# Timer-Ruler_v3.net
KiCad netlist of a schematic drawn in EAGLE
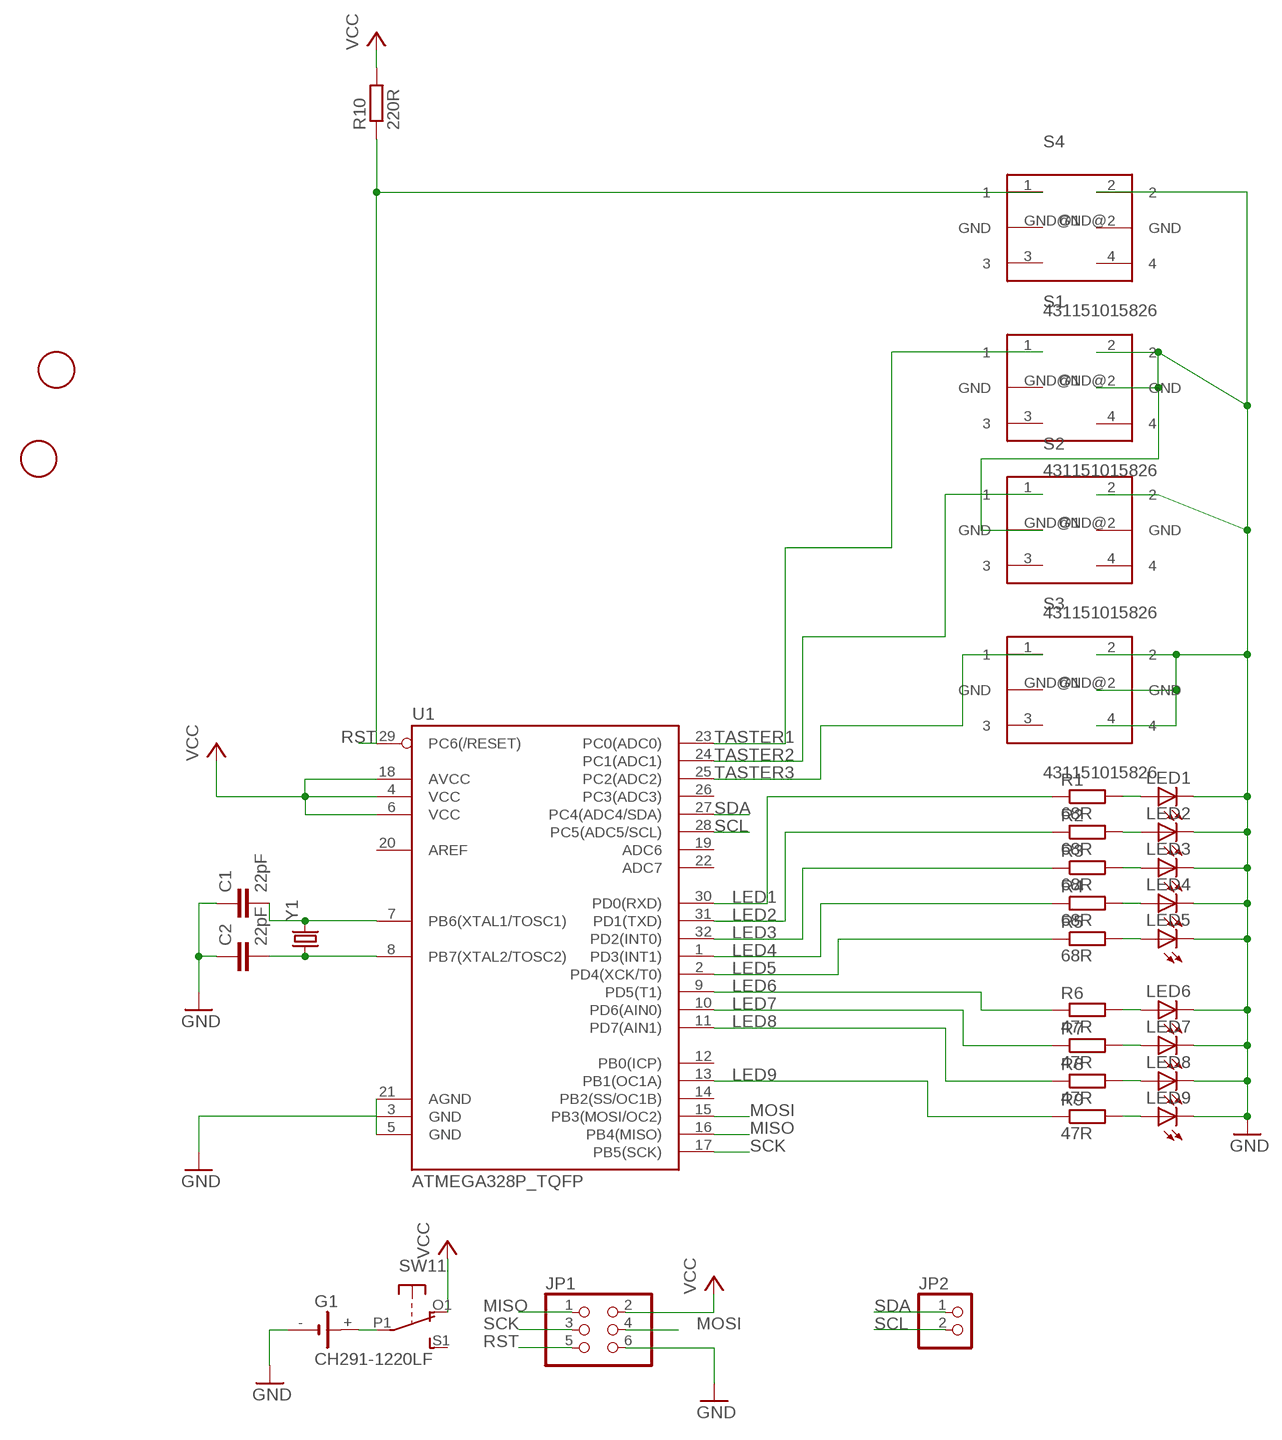
[diagram p0: schematic, sheet 1]

(export (version "E")
  (design (tool "Eeschema 10.0.6"))
  (components
    (comp (ref "C1")
      (value "22pF")
      (footprint "eagle-import:C0603")
      (libsource (lib "eagle-import") (part "C-EUC0603"))
    )
    (comp (ref "C2")
      (value "22pF")
      (footprint "eagle-import:C0603")
      (libsource (lib "eagle-import") (part "C-EUC0603"))
    )
    (comp (ref "G1")
      (value "CH291-1220LF")
      (footprint "eagle-import:CH291-1220LF")
      (libsource (lib "eagle-import") (part "CH291-1220LF"))
    )
    (comp (ref "JP1")
      (value "PINHD-2X3")
      (footprint "eagle-import:2X03")
      (libsource (lib "eagle-import") (part "PINHD-2X3"))
    )
    (comp (ref "JP2")
      (value "PINHD-1X2")
      (footprint "eagle-import:1X02")
      (libsource (lib "eagle-import") (part "PINHD-1X2"))
    )
    (comp (ref "LED1")
      (value "LEDCHIP-LED0805")
      (footprint "eagle-import:CHIP-LED0805")
      (libsource (lib "eagle-import") (part "LEDCHIP-LED0805"))
    )
    (comp (ref "LED2")
      (value "LEDCHIP-LED0805")
      (footprint "eagle-import:CHIP-LED0805")
      (libsource (lib "eagle-import") (part "LEDCHIP-LED0805"))
    )
    (comp (ref "LED3")
      (value "LEDCHIP-LED0805")
      (footprint "eagle-import:CHIP-LED0805")
      (libsource (lib "eagle-import") (part "LEDCHIP-LED0805"))
    )
    (comp (ref "LED4")
      (value "LEDCHIP-LED0805")
      (footprint "eagle-import:CHIP-LED0805")
      (libsource (lib "eagle-import") (part "LEDCHIP-LED0805"))
    )
    (comp (ref "LED5")
      (value "LEDCHIP-LED0805")
      (footprint "eagle-import:CHIP-LED0805")
      (libsource (lib "eagle-import") (part "LEDCHIP-LED0805"))
    )
    (comp (ref "LED6")
      (value "LEDCHIP-LED0805")
      (footprint "eagle-import:CHIP-LED0805")
      (libsource (lib "eagle-import") (part "LEDCHIP-LED0805"))
    )
    (comp (ref "LED7")
      (value "LEDCHIP-LED0805")
      (footprint "eagle-import:CHIP-LED0805")
      (libsource (lib "eagle-import") (part "LEDCHIP-LED0805"))
    )
    (comp (ref "LED8")
      (value "LEDCHIP-LED0805")
      (footprint "eagle-import:CHIP-LED0805")
      (libsource (lib "eagle-import") (part "LEDCHIP-LED0805"))
    )
    (comp (ref "LED9")
      (value "LEDCHIP-LED0805")
      (footprint "eagle-import:CHIP-LED0805")
      (libsource (lib "eagle-import") (part "LEDCHIP-LED0805"))
    )
    (comp (ref "R1")
      (value "68R")
      (footprint "eagle-import:R0603")
      (libsource (lib "eagle-import") (part "R-EU_R0603"))
    )
    (comp (ref "R2")
      (value "68R")
      (footprint "eagle-import:R0603")
      (libsource (lib "eagle-import") (part "R-EU_R0603"))
    )
    (comp (ref "R3")
      (value "68R")
      (footprint "eagle-import:R0603")
      (libsource (lib "eagle-import") (part "R-EU_R0603"))
    )
    (comp (ref "R4")
      (value "68R")
      (footprint "eagle-import:R0603")
      (libsource (lib "eagle-import") (part "R-EU_R0603"))
    )
    (comp (ref "R5")
      (value "68R")
      (footprint "eagle-import:R0603")
      (libsource (lib "eagle-import") (part "R-EU_R0603"))
    )
    (comp (ref "R6")
      (value "47R")
      (footprint "eagle-import:R0603")
      (libsource (lib "eagle-import") (part "R-EU_R0603"))
    )
    (comp (ref "R7")
      (value "47R")
      (footprint "eagle-import:R0603")
      (libsource (lib "eagle-import") (part "R-EU_R0603"))
    )
    (comp (ref "R8")
      (value "47R")
      (footprint "eagle-import:R0603")
      (libsource (lib "eagle-import") (part "R-EU_R0603"))
    )
    (comp (ref "R9")
      (value "47R")
      (footprint "eagle-import:R0603")
      (libsource (lib "eagle-import") (part "R-EU_R0603"))
    )
    (comp (ref "R10")
      (value "220R")
      (footprint "eagle-import:R0603")
      (libsource (lib "eagle-import") (part "R-EU_R0603"))
    )
    (comp (ref "S1")
      (value "431151015826")
      (footprint "eagle-import:431181015816")
      (libsource (lib "eagle-import") (part "431151015826"))
    )
    (comp (ref "S2")
      (value "431151015826")
      (footprint "eagle-import:431181015816")
      (libsource (lib "eagle-import") (part "431151015826"))
    )
    (comp (ref "S3")
      (value "431151015826")
      (footprint "eagle-import:431181015816")
      (libsource (lib "eagle-import") (part "431151015826"))
    )
    (comp (ref "S4")
      (value "431151015826")
      (footprint "eagle-import:431181015816")
      (libsource (lib "eagle-import") (part "431151015826"))
    )
    (comp (ref "SW1")
      (value "DPDT-EG1390")
      (footprint "eagle-import:EG1390")
      (libsource (lib "eagle-import") (part "DPDT-EG1390"))
    )
    (comp (ref "U$1")
      (value "FIDUCIAL")
      (footprint "eagle-import:FIDUCIAL_1MM")
      (libsource (lib "eagle-import") (part "FIDUCIAL"))
    )
    (comp (ref "U$2")
      (value "FIDUCIAL")
      (footprint "eagle-import:FIDUCIAL_1MM")
      (libsource (lib "eagle-import") (part "FIDUCIAL"))
    )
    (comp (ref "U1")
      (value "ATMEGA328P_TQFP")
      (footprint "eagle-import:TQFP32-08")
      (libsource (lib "eagle-import") (part "ATMEGA328P_TQFP"))
    )
    (comp (ref "Y1")
      (value "CRYSTALCRYSTAL-SMD-5X3-12.288MHZ")
      (footprint "eagle-import:CRYSTAL-SMD-5X3")
      (libsource (lib "eagle-import") (part "CRYSTALCRYSTAL-SMD-5X3-12.288MHZ"))
    )
  )
  (nets
    (net (code "1") (name "/LED1") (class "Default")
      (node (ref "R1") (pin "1") (pinfunction "1_1") (pintype "passive"))
      (node (ref "U1") (pin "30") (pinfunction "PD0(RXD)_30") (pintype "bidirectional"))
    )
    (net (code "2") (name "/LED2") (class "Default")
      (node (ref "R2") (pin "1") (pinfunction "1_1") (pintype "passive"))
      (node (ref "U1") (pin "31") (pinfunction "PD1(TXD)_31") (pintype "bidirectional"))
    )
    (net (code "3") (name "/LED3") (class "Default")
      (node (ref "R3") (pin "1") (pinfunction "1_1") (pintype "passive"))
      (node (ref "U1") (pin "32") (pinfunction "PD2(INT0)_32") (pintype "bidirectional"))
    )
    (net (code "4") (name "/LED4") (class "Default")
      (node (ref "R4") (pin "1") (pinfunction "1_1") (pintype "passive"))
      (node (ref "U1") (pin "1") (pinfunction "PD3(INT1)_1") (pintype "bidirectional"))
    )
    (net (code "5") (name "/LED5") (class "Default")
      (node (ref "R5") (pin "1") (pinfunction "1_1") (pintype "passive"))
      (node (ref "U1") (pin "2") (pinfunction "PD4(XCK/T0)_2") (pintype "bidirectional"))
    )
    (net (code "6") (name "/LED6") (class "Default")
      (node (ref "R6") (pin "1") (pinfunction "1_1") (pintype "passive"))
      (node (ref "U1") (pin "9") (pinfunction "PD5(T1)_9") (pintype "bidirectional"))
    )
    (net (code "7") (name "/LED7") (class "Default")
      (node (ref "R7") (pin "1") (pinfunction "1_1") (pintype "passive"))
      (node (ref "U1") (pin "10") (pinfunction "PD6(AIN0)_10") (pintype "bidirectional"))
    )
    (net (code "8") (name "/LED8") (class "Default")
      (node (ref "R8") (pin "1") (pinfunction "1_1") (pintype "passive"))
      (node (ref "U1") (pin "11") (pinfunction "PD7(AIN1)_11") (pintype "bidirectional"))
    )
    (net (code "9") (name "/LED9") (class "Default")
      (node (ref "R9") (pin "1") (pinfunction "1_1") (pintype "passive"))
      (node (ref "U1") (pin "13") (pinfunction "PB1(OC1A)_13") (pintype "bidirectional"))
    )
    (net (code "10") (name "/MISO") (class "Default")
      (node (ref "JP1") (pin "1") (pinfunction "1_1") (pintype "passive"))
      (node (ref "U1") (pin "16") (pinfunction "PB4(MISO)_16") (pintype "bidirectional"))
    )
    (net (code "11") (name "/MOSI") (class "Default")
      (node (ref "JP1") (pin "4") (pinfunction "4_4") (pintype "passive"))
      (node (ref "U1") (pin "15") (pinfunction "PB3(MOSI/OC2)_15") (pintype "bidirectional"))
    )
    (net (code "12") (name "/RST") (class "Default")
      (node (ref "JP1") (pin "5") (pinfunction "5_5") (pintype "passive"))
      (node (ref "R10") (pin "1") (pinfunction "1_1") (pintype "passive"))
      (node (ref "S4") (pin "1") (pinfunction "1_1") (pintype "bidirectional"))
      (node (ref "U1") (pin "29") (pinfunction "PC6(/RESET)_29") (pintype "bidirectional"))
    )
    (net (code "13") (name "/SCK") (class "Default")
      (node (ref "JP1") (pin "3") (pinfunction "3_3") (pintype "passive"))
      (node (ref "U1") (pin "17") (pinfunction "PB5(SCK)_17") (pintype "bidirectional"))
    )
    (net (code "14") (name "/SCL") (class "Default")
      (node (ref "JP2") (pin "2") (pinfunction "2_2") (pintype "passive"))
      (node (ref "U1") (pin "28") (pinfunction "PC5(ADC5/SCL)_28") (pintype "bidirectional"))
    )
    (net (code "15") (name "/SDA") (class "Default")
      (node (ref "JP2") (pin "1") (pinfunction "1_1") (pintype "passive"))
      (node (ref "U1") (pin "27") (pinfunction "PC4(ADC4/SDA)_27") (pintype "bidirectional"))
    )
    (net (code "16") (name "/TASTER1") (class "Default")
      (node (ref "S1") (pin "1") (pinfunction "1_1") (pintype "bidirectional"))
      (node (ref "U1") (pin "23") (pinfunction "PC0(ADC0)_23") (pintype "bidirectional"))
    )
    (net (code "17") (name "/TASTER2") (class "Default")
      (node (ref "S2") (pin "1") (pinfunction "1_1") (pintype "bidirectional"))
      (node (ref "U1") (pin "24") (pinfunction "PC1(ADC1)_24") (pintype "bidirectional"))
    )
    (net (code "18") (name "/TASTER3") (class "Default")
      (node (ref "S3") (pin "1") (pinfunction "1_1") (pintype "bidirectional"))
      (node (ref "U1") (pin "25") (pinfunction "PC2(ADC2)_25") (pintype "bidirectional"))
    )
    (net (code "19") (name "GND") (class "Default")
      (node (ref "C1") (pin "1") (pinfunction "1_1") (pintype "passive"))
      (node (ref "C2") (pin "1") (pinfunction "1_1") (pintype "passive"))
      (node (ref "G1") (pin "-") (pinfunction "-_-") (pintype "passive"))
      (node (ref "JP1") (pin "6") (pinfunction "6_6") (pintype "passive"))
      (node (ref "LED1") (pin "C") (pinfunction "C_C") (pintype "passive"))
      (node (ref "LED2") (pin "C") (pinfunction "C_C") (pintype "passive"))
      (node (ref "LED3") (pin "C") (pinfunction "C_C") (pintype "passive"))
      (node (ref "LED4") (pin "C") (pinfunction "C_C") (pintype "passive"))
      (node (ref "LED5") (pin "C") (pinfunction "C_C") (pintype "passive"))
      (node (ref "LED6") (pin "C") (pinfunction "C_C") (pintype "passive"))
      (node (ref "LED7") (pin "C") (pinfunction "C_C") (pintype "passive"))
      (node (ref "LED8") (pin "C") (pinfunction "C_C") (pintype "passive"))
      (node (ref "LED9") (pin "C") (pinfunction "C_C") (pintype "passive"))
      (node (ref "S1") (pin "2") (pinfunction "2_2") (pintype "bidirectional"))
      (node (ref "S1") (pin "GND@2") (pinfunction "GND_GND@2") (pintype "bidirectional"))
      (node (ref "S2") (pin "2") (pinfunction "2_2") (pintype "bidirectional"))
      (node (ref "S2") (pin "GND@1") (pinfunction "GND_GND@1") (pintype "bidirectional"))
      (node (ref "S3") (pin "2") (pinfunction "2_2") (pintype "bidirectional"))
      (node (ref "S3") (pin "4") (pinfunction "4_4") (pintype "bidirectional"))
      (node (ref "S3") (pin "GND@2") (pinfunction "GND_GND@2") (pintype "bidirectional"))
      (node (ref "S4") (pin "2") (pinfunction "2_2") (pintype "bidirectional"))
      (node (ref "U1") (pin "3") (pinfunction "GND_3") (pintype "bidirectional"))
    )
    (net (code "20") (name "Net-(LED1-PadA)") (class "Default")
      (node (ref "LED1") (pin "A") (pinfunction "A_A") (pintype "passive"))
      (node (ref "R1") (pin "2") (pinfunction "2_2") (pintype "passive"))
    )
    (net (code "21") (name "Net-(LED2-PadA)") (class "Default")
      (node (ref "LED2") (pin "A") (pinfunction "A_A") (pintype "passive"))
      (node (ref "R2") (pin "2") (pinfunction "2_2") (pintype "passive"))
    )
    (net (code "22") (name "Net-(LED3-PadA)") (class "Default")
      (node (ref "LED3") (pin "A") (pinfunction "A_A") (pintype "passive"))
      (node (ref "R3") (pin "2") (pinfunction "2_2") (pintype "passive"))
    )
    (net (code "23") (name "Net-(LED4-PadA)") (class "Default")
      (node (ref "LED4") (pin "A") (pinfunction "A_A") (pintype "passive"))
      (node (ref "R4") (pin "2") (pinfunction "2_2") (pintype "passive"))
    )
    (net (code "24") (name "Net-(LED5-PadA)") (class "Default")
      (node (ref "LED5") (pin "A") (pinfunction "A_A") (pintype "passive"))
      (node (ref "R5") (pin "2") (pinfunction "2_2") (pintype "passive"))
    )
    (net (code "25") (name "Net-(LED6-PadA)") (class "Default")
      (node (ref "LED6") (pin "A") (pinfunction "A_A") (pintype "passive"))
      (node (ref "R6") (pin "2") (pinfunction "2_2") (pintype "passive"))
    )
    (net (code "26") (name "Net-(LED7-PadA)") (class "Default")
      (node (ref "LED7") (pin "A") (pinfunction "A_A") (pintype "passive"))
      (node (ref "R7") (pin "2") (pinfunction "2_2") (pintype "passive"))
    )
    (net (code "27") (name "Net-(LED8-PadA)") (class "Default")
      (node (ref "LED8") (pin "A") (pinfunction "A_A") (pintype "passive"))
      (node (ref "R8") (pin "2") (pinfunction "2_2") (pintype "passive"))
    )
    (net (code "28") (name "Net-(LED9-PadA)") (class "Default")
      (node (ref "LED9") (pin "A") (pinfunction "A_A") (pintype "passive"))
      (node (ref "R9") (pin "2") (pinfunction "2_2") (pintype "passive"))
    )
    (net (code "29") (name "Net-(SW1A-P)") (class "Default")
      (node (ref "G1") (pin "+") (pinfunction "+_+") (pintype "passive"))
      (node (ref "SW1") (pin "P1") (pinfunction "P_P1") (pintype "passive"))
    )
    (net (code "30") (name "Net-(U1-AGND)") (class "Default")
      (node (ref "U1") (pin "21") (pinfunction "AGND_21") (pintype "bidirectional"))
      (node (ref "U1") (pin "5") (pinfunction "GND_5") (pintype "bidirectional"))
    )
    (net (code "31") (name "Net-(U1-PB6(XTAL1{slash}TOSC1))") (class "Default")
      (node (ref "C1") (pin "2") (pinfunction "2_2") (pintype "passive"))
      (node (ref "U1") (pin "7") (pinfunction "PB6(XTAL1/TOSC1)_7") (pintype "bidirectional"))
      (node (ref "Y1") (pin "3") (pinfunction "2_3") (pintype "passive"))
    )
    (net (code "32") (name "Net-(U1-PB7(XTAL2{slash}TOSC2))") (class "Default")
      (node (ref "C2") (pin "2") (pinfunction "2_2") (pintype "passive"))
      (node (ref "U1") (pin "8") (pinfunction "PB7(XTAL2/TOSC2)_8") (pintype "bidirectional"))
      (node (ref "Y1") (pin "1") (pinfunction "1_1") (pintype "passive"))
    )
    (net (code "33") (name "VCC") (class "Default")
      (node (ref "JP1") (pin "2") (pinfunction "2_2") (pintype "passive"))
      (node (ref "R10") (pin "2") (pinfunction "2_2") (pintype "passive"))
      (node (ref "SW1") (pin "O1") (pinfunction "O_O1") (pintype "passive"))
      (node (ref "U1") (pin "18") (pinfunction "AVCC_18") (pintype "bidirectional"))
      (node (ref "U1") (pin "4") (pinfunction "VCC_4") (pintype "bidirectional"))
      (node (ref "U1") (pin "6") (pinfunction "VCC_6") (pintype "bidirectional"))
    )
    (net (code "34") (name "unconnected-(S1-GND-PadGND@1)") (class "Default")
      (node (ref "S1") (pin "GND@1") (pinfunction "GND_GND@1") (pintype "bidirectional"))
    )
    (net (code "35") (name "unconnected-(S1-Pad3)") (class "Default")
      (node (ref "S1") (pin "3") (pinfunction "3_3") (pintype "bidirectional"))
    )
    (net (code "36") (name "unconnected-(S1-Pad4)") (class "Default")
      (node (ref "S1") (pin "4") (pinfunction "4_4") (pintype "bidirectional"))
    )
    (net (code "37") (name "unconnected-(S2-GND-PadGND@2)") (class "Default")
      (node (ref "S2") (pin "GND@2") (pinfunction "GND_GND@2") (pintype "bidirectional"))
    )
    (net (code "38") (name "unconnected-(S2-Pad3)") (class "Default")
      (node (ref "S2") (pin "3") (pinfunction "3_3") (pintype "bidirectional"))
    )
    (net (code "39") (name "unconnected-(S2-Pad4)") (class "Default")
      (node (ref "S2") (pin "4") (pinfunction "4_4") (pintype "bidirectional"))
    )
    (net (code "40") (name "unconnected-(S3-GND-PadGND@1)") (class "Default")
      (node (ref "S3") (pin "GND@1") (pinfunction "GND_GND@1") (pintype "bidirectional"))
    )
    (net (code "41") (name "unconnected-(S3-Pad3)") (class "Default")
      (node (ref "S3") (pin "3") (pinfunction "3_3") (pintype "bidirectional"))
    )
    (net (code "42") (name "unconnected-(S4-GND-PadGND@1)") (class "Default")
      (node (ref "S4") (pin "GND@1") (pinfunction "GND_GND@1") (pintype "bidirectional"))
    )
    (net (code "43") (name "unconnected-(S4-GND-PadGND@2)") (class "Default")
      (node (ref "S4") (pin "GND@2") (pinfunction "GND_GND@2") (pintype "bidirectional"))
    )
    (net (code "44") (name "unconnected-(S4-Pad3)") (class "Default")
      (node (ref "S4") (pin "3") (pinfunction "3_3") (pintype "bidirectional"))
    )
    (net (code "45") (name "unconnected-(S4-Pad4)") (class "Default")
      (node (ref "S4") (pin "4") (pinfunction "4_4") (pintype "bidirectional"))
    )
    (net (code "46") (name "unconnected-(SW1A-S-PadS1)") (class "Default")
      (node (ref "SW1") (pin "S1") (pinfunction "S_S1") (pintype "passive"))
    )
    (net (code "47") (name "unconnected-(U1-ADC6-Pad19)") (class "Default")
      (node (ref "U1") (pin "19") (pinfunction "ADC6_19") (pintype "bidirectional"))
    )
    (net (code "48") (name "unconnected-(U1-ADC7-Pad22)") (class "Default")
      (node (ref "U1") (pin "22") (pinfunction "ADC7_22") (pintype "bidirectional"))
    )
    (net (code "49") (name "unconnected-(U1-AREF-Pad20)") (class "Default")
      (node (ref "U1") (pin "20") (pinfunction "AREF_20") (pintype "bidirectional"))
    )
    (net (code "50") (name "unconnected-(U1-PB0(ICP)-Pad12)") (class "Default")
      (node (ref "U1") (pin "12") (pinfunction "PB0(ICP)_12") (pintype "bidirectional"))
    )
    (net (code "51") (name "unconnected-(U1-PB2(SS{slash}OC1B)-Pad14)") (class "Default")
      (node (ref "U1") (pin "14") (pinfunction "PB2(SS/OC1B)_14") (pintype "bidirectional"))
    )
    (net (code "52") (name "unconnected-(U1-PC3(ADC3)-Pad26)") (class "Default")
      (node (ref "U1") (pin "26") (pinfunction "PC3(ADC3)_26") (pintype "bidirectional"))
    )
  )
)
